# design.net
KiCad netlist of a schematic drawn in EasyEDA Pro
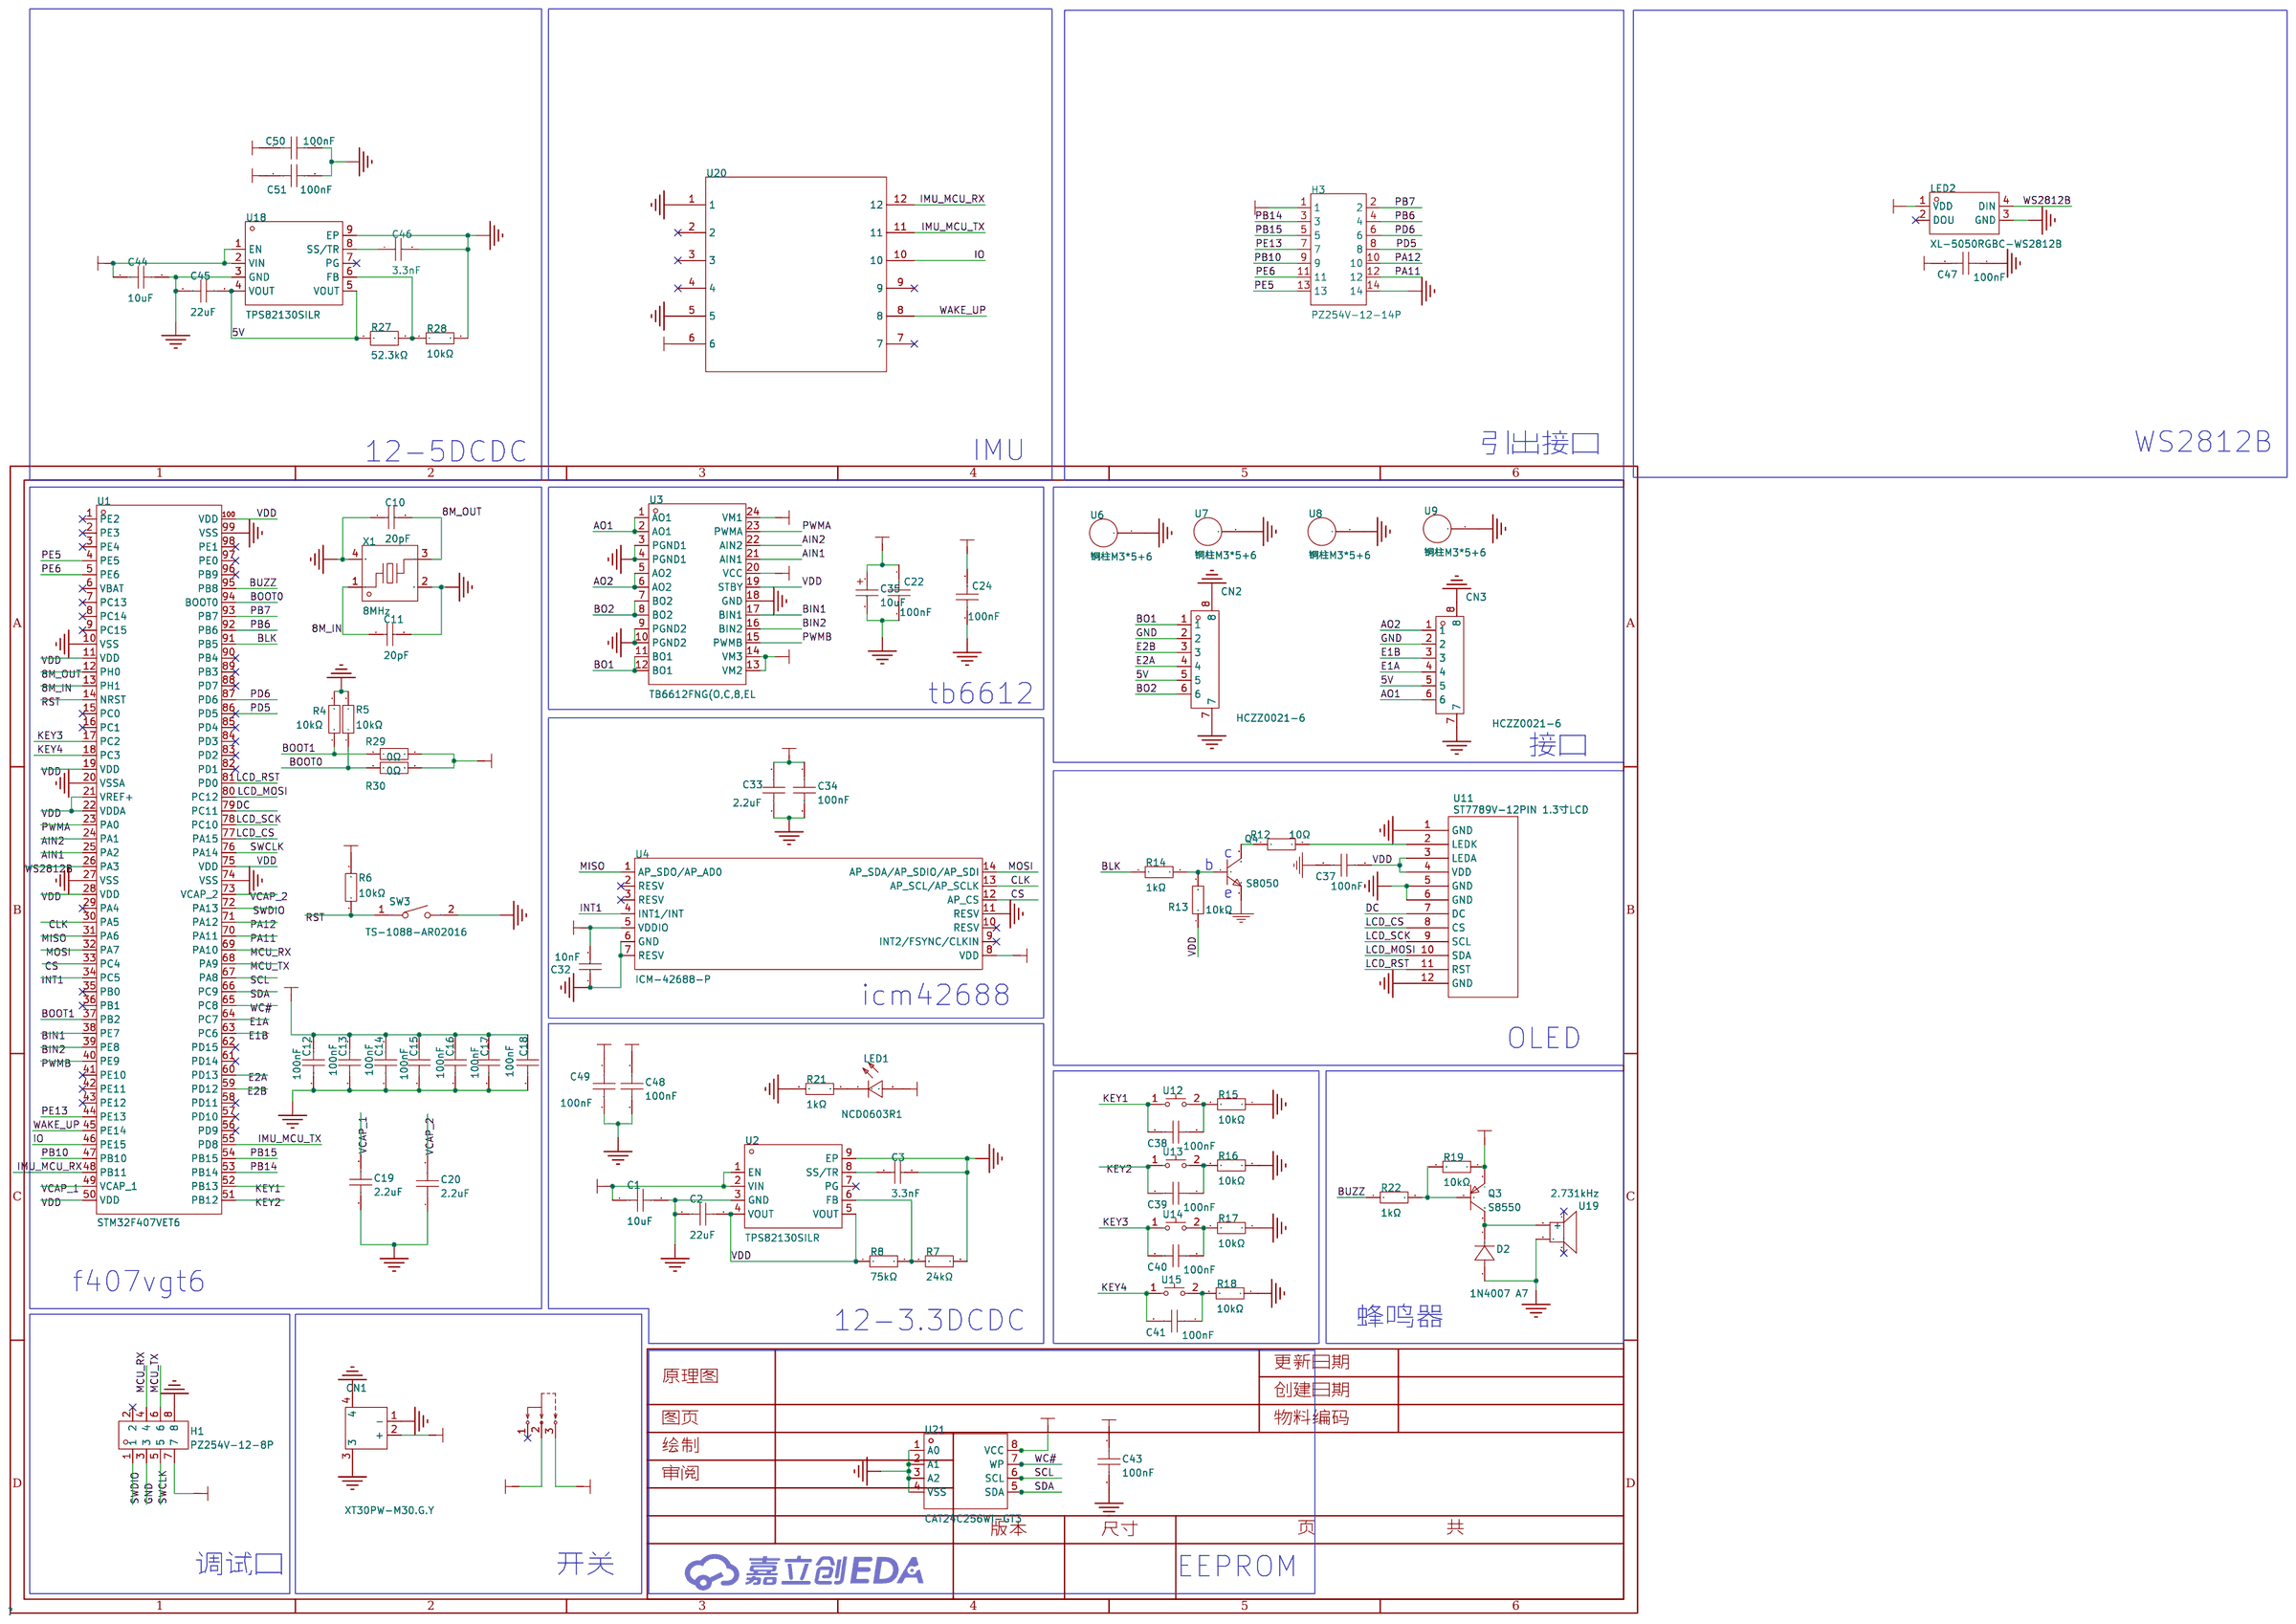
[diagram p0: schematic sheet]

(export (version "E")
  (design (tool "Eeschema 10.0.6"))
  (components
    (comp (ref "C1")
      (value "10uF")
      (footprint "easyedapro:C0805")
      (description "容值:10uF;精度:±10%;额定电压:50V;材质(温度系数):X5R;")
      (fields
        (field (name "Manufacturer Part") "GRM21BR61H106KE43L")
        (field (name "Manufacturer") "muRata(村田)")
      )
      (libsource (lib "easyedapro") (part "GRM21BR61H106KE43L"))
    )
    (comp (ref "C2")
      (value "22uF")
      (footprint "easyedapro:C0805")
      (description "容值:22uF;精度:±20%;额定电压:35V;材质(温度系数):X5R;")
      (fields
        (field (name "Manufacturer Part") "CGA0805X5R226M350MT")
        (field (name "Manufacturer") "HRE(芯声)")
      )
      (libsource (lib "easyedapro") (part "CGA0805X5R226M350MT"))
    )
    (comp (ref "C3")
      (value "3.3nF")
      (footprint "easyedapro:C0603")
      (description "容值:3.3nF;精度:±10%;额定电压:50V;材质(温度系数):X7R;")
      (fields
        (field (name "Manufacturer Part") "CC0603KRX7R9BB332")
        (field (name "Manufacturer") "YAGEO(国巨)")
      )
      (libsource (lib "easyedapro") (part "CC0603KRX7R9BB332"))
    )
    (comp (ref "C10")
      (value "20pF")
      (footprint "easyedapro:C0603")
      (description "容值:20pF;精度:±5%;额定电压:50V;材质(温度系数):C0G;")
      (fields
        (field (name "Manufacturer Part") "CL10C200JB8NNNC")
        (field (name "Manufacturer") "SAMSUNG(三星)")
      )
      (libsource (lib "easyedapro") (part "CL10C200JB8NNNC"))
    )
    (comp (ref "C11")
      (value "20pF")
      (footprint "easyedapro:C0603")
      (description "容值:20pF;精度:±5%;额定电压:50V;材质(温度系数):C0G;")
      (fields
        (field (name "Manufacturer Part") "CL10C200JB8NNNC")
        (field (name "Manufacturer") "SAMSUNG(三星)")
      )
      (libsource (lib "easyedapro") (part "CL10C200JB8NNNC"))
    )
    (comp (ref "C12")
      (value "100nF")
      (footprint "easyedapro:C0603")
      (description "容值:100nF;精度:±10%;额定电压:50V;材质(温度系数):X7R;")
      (fields
        (field (name "Manufacturer Part") "CGA0603X7R104K500JT")
        (field (name "Manufacturer") "HRE(芯声)")
      )
      (libsource (lib "easyedapro") (part "CGA0603X7R104K500JT"))
    )
    (comp (ref "C13")
      (value "100nF")
      (footprint "easyedapro:C0603")
      (description "容值:100nF;精度:±10%;额定电压:50V;材质(温度系数):X7R;")
      (fields
        (field (name "Manufacturer Part") "CGA0603X7R104K500JT")
        (field (name "Manufacturer") "HRE(芯声)")
      )
      (libsource (lib "easyedapro") (part "CGA0603X7R104K500JT"))
    )
    (comp (ref "C14")
      (value "100nF")
      (footprint "easyedapro:C0603")
      (description "容值:100nF;精度:±10%;额定电压:50V;材质(温度系数):X7R;")
      (fields
        (field (name "Manufacturer Part") "CGA0603X7R104K500JT")
        (field (name "Manufacturer") "HRE(芯声)")
      )
      (libsource (lib "easyedapro") (part "CGA0603X7R104K500JT"))
    )
    (comp (ref "C15")
      (value "100nF")
      (footprint "easyedapro:C0603")
      (description "容值:100nF;精度:±10%;额定电压:50V;材质(温度系数):X7R;")
      (fields
        (field (name "Manufacturer Part") "CGA0603X7R104K500JT")
        (field (name "Manufacturer") "HRE(芯声)")
      )
      (libsource (lib "easyedapro") (part "CGA0603X7R104K500JT"))
    )
    (comp (ref "C16")
      (value "100nF")
      (footprint "easyedapro:C0603")
      (description "容值:100nF;精度:±10%;额定电压:50V;材质(温度系数):X7R;")
      (fields
        (field (name "Manufacturer Part") "CGA0603X7R104K500JT")
        (field (name "Manufacturer") "HRE(芯声)")
      )
      (libsource (lib "easyedapro") (part "CGA0603X7R104K500JT"))
    )
    (comp (ref "C17")
      (value "100nF")
      (footprint "easyedapro:C0603")
      (description "容值:100nF;精度:±10%;额定电压:50V;材质(温度系数):X7R;")
      (fields
        (field (name "Manufacturer Part") "CGA0603X7R104K500JT")
        (field (name "Manufacturer") "HRE(芯声)")
      )
      (libsource (lib "easyedapro") (part "CGA0603X7R104K500JT"))
    )
    (comp (ref "C18")
      (value "100nF")
      (footprint "easyedapro:C0603")
      (description "容值:100nF;精度:±10%;额定电压:50V;材质(温度系数):X7R;")
      (fields
        (field (name "Manufacturer Part") "CGA0603X7R104K500JT")
        (field (name "Manufacturer") "HRE(芯声)")
      )
      (libsource (lib "easyedapro") (part "CGA0603X7R104K500JT"))
    )
    (comp (ref "C19")
      (value "2.2uF")
      (footprint "easyedapro:C0603")
      (description "容值:2.2uF;精度:±10%;额定电压:50V;材质(温度系数):X5R;")
      (fields
        (field (name "Manufacturer Part") "CL10A225KB8NNNC")
        (field (name "Manufacturer") "SAMSUNG(三星)")
      )
      (libsource (lib "easyedapro") (part "CL10A225KB8NNNC"))
    )
    (comp (ref "C20")
      (value "2.2uF")
      (footprint "easyedapro:C0603")
      (description "容值:2.2uF;精度:±10%;额定电压:50V;材质(温度系数):X5R;")
      (fields
        (field (name "Manufacturer Part") "CL10A225KB8NNNC")
        (field (name "Manufacturer") "SAMSUNG(三星)")
      )
      (libsource (lib "easyedapro") (part "CL10A225KB8NNNC"))
    )
    (comp (ref "C22")
      (value "100nF")
      (footprint "easyedapro:C0603")
      (description "容值:100nF;精度:±10%;额定电压:50V;材质(温度系数):X7R;")
      (fields
        (field (name "Manufacturer Part") "CGA0603X7R104K500JT")
        (field (name "Manufacturer") "HRE(芯声)")
      )
      (libsource (lib "easyedapro") (part "CGA0603X7R104K500JT"))
    )
    (comp (ref "C24")
      (value "100nF")
      (footprint "easyedapro:C0603")
      (description "容值:100nF;精度:±10%;额定电压:50V;材质(温度系数):X7R;")
      (fields
        (field (name "Manufacturer Part") "CGA0603X7R104K500JT")
        (field (name "Manufacturer") "HRE(芯声)")
      )
      (libsource (lib "easyedapro") (part "CGA0603X7R104K500JT"))
    )
    (comp (ref "C32")
      (value "10nF")
      (footprint "easyedapro:C0603")
      (description "容值:10nF;精度:±10%;额定电压:50V;材质(温度系数):X7R;")
      (fields
        (field (name "Manufacturer Part") "CC0603KRX7R9BB103")
        (field (name "Manufacturer") "YAGEO(国巨)")
      )
      (libsource (lib "easyedapro") (part "CC0603KRX7R9BB103"))
    )
    (comp (ref "C33")
      (value "2.2uF")
      (footprint "easyedapro:C0603")
      (description "容值:2.2uF;精度:±10%;额定电压:50V;材质(温度系数):X5R;")
      (fields
        (field (name "Manufacturer Part") "CL10A225KB8NNNC")
        (field (name "Manufacturer") "SAMSUNG(三星)")
      )
      (libsource (lib "easyedapro") (part "CL10A225KB8NNNC"))
    )
    (comp (ref "C34")
      (value "100nF")
      (footprint "easyedapro:C0603")
      (description "容值:100nF;精度:±10%;额定电压:50V;材质(温度系数):X7R;")
      (fields
        (field (name "Manufacturer Part") "CGA0603X7R104K500JT")
        (field (name "Manufacturer") "HRE(芯声)")
      )
      (libsource (lib "easyedapro") (part "CGA0603X7R104K500JT"))
    )
    (comp (ref "C35")
      (value "10uF")
      (footprint "easyedapro:CAP-SMD_L3.2-W1.6-RD-C7171")
      (description "容值:10uF;精度:±10%;额定电压:16V;等效串联电阻:3Ω@100kHz;")
      (fields (field (name "Manufacturer Part") "TAJA106K016RNJ") (field (name "Manufacturer") "Kyocera AVX"))
      (libsource (lib "easyedapro") (part "TAJA106K016RNJ"))
    )
    (comp (ref "C37")
      (value "100nF")
      (footprint "easyedapro:C0603")
      (description "容值:100nF;精度:±10%;额定电压:50V;材质(温度系数):X7R;")
      (fields
        (field (name "Manufacturer Part") "CGA0603X7R104K500JT")
        (field (name "Manufacturer") "HRE(芯声)")
      )
      (libsource (lib "easyedapro") (part "CGA0603X7R104K500JT"))
    )
    (comp (ref "C38")
      (value "100nF")
      (footprint "easyedapro:C0603")
      (description "容值:100nF;精度:±10%;额定电压:50V;材质(温度系数):X7R;")
      (fields
        (field (name "Manufacturer Part") "CGA0603X7R104K500JT")
        (field (name "Manufacturer") "HRE(芯声)")
      )
      (libsource (lib "easyedapro") (part "CGA0603X7R104K500JT"))
    )
    (comp (ref "C39")
      (value "100nF")
      (footprint "easyedapro:C0603")
      (description "容值:100nF;精度:±10%;额定电压:50V;材质(温度系数):X7R;")
      (fields
        (field (name "Manufacturer Part") "CGA0603X7R104K500JT")
        (field (name "Manufacturer") "HRE(芯声)")
      )
      (libsource (lib "easyedapro") (part "CGA0603X7R104K500JT"))
    )
    (comp (ref "C40")
      (value "100nF")
      (footprint "easyedapro:C0603")
      (description "容值:100nF;精度:±10%;额定电压:50V;材质(温度系数):X7R;")
      (fields
        (field (name "Manufacturer Part") "CGA0603X7R104K500JT")
        (field (name "Manufacturer") "HRE(芯声)")
      )
      (libsource (lib "easyedapro") (part "CGA0603X7R104K500JT"))
    )
    (comp (ref "C41")
      (value "100nF")
      (footprint "easyedapro:C0603")
      (description "容值:100nF;精度:±10%;额定电压:50V;材质(温度系数):X7R;")
      (fields
        (field (name "Manufacturer Part") "CGA0603X7R104K500JT")
        (field (name "Manufacturer") "HRE(芯声)")
      )
      (libsource (lib "easyedapro") (part "CGA0603X7R104K500JT"))
    )
    (comp (ref "C43")
      (value "100nF")
      (footprint "easyedapro:C0603")
      (description "容值:100nF;精度:±10%;额定电压:50V;材质(温度系数):X7R;")
      (fields
        (field (name "Manufacturer Part") "CGA0603X7R104K500JT")
        (field (name "Manufacturer") "HRE(芯声)")
      )
      (libsource (lib "easyedapro") (part "CGA0603X7R104K500JT"))
    )
    (comp (ref "C44")
      (value "10uF")
      (footprint "easyedapro:C0805")
      (description "容值:10uF;精度:±10%;额定电压:50V;材质(温度系数):X5R;")
      (fields
        (field (name "Manufacturer Part") "GRM21BR61H106KE43L")
        (field (name "Manufacturer") "muRata(村田)")
      )
      (libsource (lib "easyedapro") (part "GRM21BR61H106KE43L"))
    )
    (comp (ref "C45")
      (value "22uF")
      (footprint "easyedapro:C0805")
      (description "容值:22uF;精度:±20%;额定电压:35V;材质(温度系数):X5R;")
      (fields
        (field (name "Manufacturer Part") "CGA0805X5R226M350MT")
        (field (name "Manufacturer") "HRE(芯声)")
      )
      (libsource (lib "easyedapro") (part "CGA0805X5R226M350MT"))
    )
    (comp (ref "C46")
      (value "3.3nF")
      (footprint "easyedapro:C0603")
      (description "容值:3.3nF;精度:±10%;额定电压:50V;材质(温度系数):X7R;")
      (fields
        (field (name "Manufacturer Part") "CC0603KRX7R9BB332")
        (field (name "Manufacturer") "YAGEO(国巨)")
      )
      (libsource (lib "easyedapro") (part "CC0603KRX7R9BB332"))
    )
    (comp (ref "C47")
      (value "100nF")
      (footprint "easyedapro:C0603")
      (description "容值:100nF;精度:±10%;额定电压:50V;材质(温度系数):X7R;")
      (fields
        (field (name "Manufacturer Part") "CGA0603X7R104K500JT")
        (field (name "Manufacturer") "HRE(芯声)")
      )
      (libsource (lib "easyedapro") (part "CGA0603X7R104K500JT"))
    )
    (comp (ref "C48")
      (value "100nF")
      (footprint "easyedapro:C0603")
      (description "容值:100nF;精度:±10%;额定电压:50V;材质(温度系数):X7R;")
      (fields
        (field (name "Manufacturer Part") "CGA0603X7R104K500JT")
        (field (name "Manufacturer") "HRE(芯声)")
      )
      (libsource (lib "easyedapro") (part "CGA0603X7R104K500JT"))
    )
    (comp (ref "C49")
      (value "100nF")
      (footprint "easyedapro:C0603")
      (description "容值:100nF;精度:±10%;额定电压:50V;材质(温度系数):X7R;")
      (fields
        (field (name "Manufacturer Part") "CGA0603X7R104K500JT")
        (field (name "Manufacturer") "HRE(芯声)")
      )
      (libsource (lib "easyedapro") (part "CGA0603X7R104K500JT"))
    )
    (comp (ref "C50")
      (value "100nF")
      (footprint "easyedapro:C0603")
      (description "容值:100nF;精度:±10%;额定电压:50V;材质(温度系数):X7R;")
      (fields
        (field (name "Manufacturer Part") "CGA0603X7R104K500JT")
        (field (name "Manufacturer") "HRE(芯声)")
      )
      (libsource (lib "easyedapro") (part "CGA0603X7R104K500JT"))
    )
    (comp (ref "C51")
      (value "100nF")
      (footprint "easyedapro:C0603")
      (description "容值:100nF;精度:±10%;额定电压:50V;材质(温度系数):X7R;")
      (fields
        (field (name "Manufacturer Part") "CGA0603X7R104K500JT")
        (field (name "Manufacturer") "HRE(芯声)")
      )
      (libsource (lib "easyedapro") (part "CGA0603X7R104K500JT"))
    )
    (comp (ref "CN1")
      (value "XT30PW-M30.G.Y")
      (footprint "easyedapro:CONN-TH_XT30PW-M")
      (description "类别:-;类型1:-;")
      (fields (field (name "Manufacturer") "AMASS(艾迈斯)"))
      (libsource (lib "easyedapro") (part "XT30PW-M"))
    )
    (comp (ref "CN2")
      (value "HCZZ0021-6")
      (footprint "easyedapro:CONN-SMD_HCZZ0021-6")
      (fields (field (name "Manufacturer") "HC(虹成电子)"))
      (libsource (lib "easyedapro") (part "HCZZ0021-6"))
    )
    (comp (ref "CN3")
      (value "HCZZ0021-6")
      (footprint "easyedapro:CONN-SMD_HCZZ0021-6")
      (fields (field (name "Manufacturer") "HC(虹成电子)"))
      (libsource (lib "easyedapro") (part "HCZZ0021-6"))
    )
    (comp (ref "D2")
      (value "1N4007 A7")
      (footprint "easyedapro:SOD-123FL_L2.8-W1.8-LS3.7-RD")
      (description "二极管配置:-;正向压降(Vf):1V@1A;直流反向耐压(Vr):1kV;整流电流:1A;")
      (fields (field (name "Manufacturer") "MSKSEMI(美森科)"))
      (libsource (lib "easyedapro") (part "1N4007 A7"))
    )
    (comp (ref "H1")
      (value "PZ254V-12-8P")
      (footprint "easyedapro:HDR-TH_8P-P2.54-V-M-R2-C4-S2.54")
      (fields (field (name "Manufacturer") "XFCN(兴飞)"))
      (libsource (lib "easyedapro") (part "PZ254V-12-8P"))
    )
    (comp (ref "H3")
      (value "PZ254V-12-14P")
      (footprint "easyedapro:HDR-TH_14P-P2.54-V-M-R2-C7-S2.54")
      (fields (field (name "Manufacturer") "XFCN(兴飞)"))
      (libsource (lib "easyedapro") (part "PZ254V-12-14P"))
    )
    (comp (ref "LED1")
      (value "NCD0603R1")
      (footprint "easyedapro:LED0603-RD")
      (fields (field (name "Manufacturer") "国星光电"))
      (libsource (lib "easyedapro") (part "FC-DA1608HRK-620D"))
    )
    (comp (ref "LED2")
      (value "XL-5050RGBC-WS2812B")
      (footprint "easyedapro:LED-SMD_4P-L5.0-W5.0-BL_XL-5050RGBC")
      (description "5050七彩幻彩透明贴片LED灯珠 5050 幻彩透明四脚 ws2812B 内置驱动IC")
      (fields (field (name "Manufacturer") "XINGLIGHT(成兴光)"))
      (libsource (lib "easyedapro") (part "XL-5050RGBC-WS2812B"))
    )
    (comp (ref "Q3")
      (value "S8550")
      (footprint "easyedapro:SOT-23-3_L2.9-W1.6-P1.90-LS2.8-BR")
      (description "晶体管类型:PNP;集电极电流(Ic):500mA;集射极击穿电压(Vceo):25V;功率(Pd):300mW;")
      (fields (field (name "Manufacturer") "Hottech(合科泰)"))
      (libsource (lib "easyedapro") (part "S8550_C181159"))
    )
    (comp (ref "Q4")
      (value "S8050")
      (footprint "easyedapro:SOT-23-3_L2.9-W1.3-P1.90-LS2.3-BR")
      (description "晶体管类型:NPN;集电极电流(Ic):500mA;集射极击穿电压(Vceo):25V;功率(Pd):300mW;直流电流增益(hFE@Ic,Vce):120@50mA,1.0V;")
      (fields (field (name "Manufacturer") "宏迦橙"))
      (libsource (lib "easyedapro") (part "S8050_C20069125"))
    )
    (comp (ref "R4")
      (value "10kΩ")
      (footprint "easyedapro:R0603")
      (description "电阻类型:厚膜电阻;阻值:10kΩ;精度:±1%;功率:100mW;最大工作电压:75V;温度系数:±100ppm/°C;")
      (fields
        (field (name "Manufacturer Part") "0603WAF1002T5E")
        (field (name "Manufacturer") "UNI-ROYAL(厚声)")
      )
      (libsource (lib "easyedapro") (part "0603WAF1002T5E"))
    )
    (comp (ref "R5")
      (value "10kΩ")
      (footprint "easyedapro:R0603")
      (description "电阻类型:厚膜电阻;阻值:10kΩ;精度:±1%;功率:100mW;最大工作电压:75V;温度系数:±100ppm/°C;")
      (fields
        (field (name "Manufacturer Part") "0603WAF1002T5E")
        (field (name "Manufacturer") "UNI-ROYAL(厚声)")
      )
      (libsource (lib "easyedapro") (part "0603WAF1002T5E"))
    )
    (comp (ref "R6")
      (value "10kΩ")
      (footprint "easyedapro:R0603")
      (description "电阻类型:厚膜电阻;阻值:10kΩ;精度:±1%;功率:100mW;最大工作电压:75V;温度系数:±100ppm/°C;")
      (fields
        (field (name "Manufacturer Part") "0603WAF1002T5E")
        (field (name "Manufacturer") "UNI-ROYAL(厚声)")
      )
      (libsource (lib "easyedapro") (part "0603WAF1002T5E"))
    )
    (comp (ref "R7")
      (value "24kΩ")
      (footprint "easyedapro:R0603")
      (description "电阻类型:厚膜电阻;阻值:24kΩ;精度:±1%;功率:100mW;最大工作电压:75V;温度系数:±100ppm/°C;")
      (fields
        (field (name "Manufacturer Part") "0603WAF2402T5E")
        (field (name "Manufacturer") "UNI-ROYAL(厚声)")
      )
      (libsource (lib "easyedapro") (part "0603WAF2402T5E"))
    )
    (comp (ref "R8")
      (value "75kΩ")
      (footprint "easyedapro:R0603")
      (description "电阻类型:厚膜电阻;阻值:75kΩ;精度:±1%;功率:100mW;最大工作电压:75V;温度系数:±100ppm/°C;")
      (fields
        (field (name "Manufacturer Part") "0603WAF7502T5E")
        (field (name "Manufacturer") "UNI-ROYAL(厚声)")
      )
      (libsource (lib "easyedapro") (part "0603WAF7502T5E"))
    )
    (comp (ref "R12")
      (value "10Ω")
      (footprint "easyedapro:R0603")
      (description "电阻类型:厚膜电阻;阻值:10Ω;精度:±1%;功率:100mW;最大工作电压:75V;温度系数:±400ppm/°C;")
      (fields
        (field (name "Manufacturer Part") "0603WAF100JT5E")
        (field (name "Manufacturer") "UNI-ROYAL(厚声)")
      )
      (libsource (lib "easyedapro") (part "0603WAF100JT5E"))
    )
    (comp (ref "R13")
      (value "10kΩ")
      (footprint "easyedapro:R0603")
      (description "电阻类型:厚膜电阻;阻值:10kΩ;精度:±1%;功率:100mW;最大工作电压:75V;温度系数:±100ppm/°C;")
      (fields
        (field (name "Manufacturer Part") "0603WAF1002T5E")
        (field (name "Manufacturer") "UNI-ROYAL(厚声)")
      )
      (libsource (lib "easyedapro") (part "0603WAF1002T5E"))
    )
    (comp (ref "R14")
      (value "1kΩ")
      (footprint "easyedapro:R0603")
      (description "电阻类型:厚膜电阻;阻值:1kΩ;精度:±1%;功率:100mW;最大工作电压:75V;温度系数:±100ppm/°C;")
      (fields
        (field (name "Manufacturer Part") "0603WAF1001T5E")
        (field (name "Manufacturer") "UNI-ROYAL(厚声)")
      )
      (libsource (lib "easyedapro") (part "0603WAF1001T5E"))
    )
    (comp (ref "R15")
      (value "10kΩ")
      (footprint "easyedapro:R0603")
      (description "电阻类型:厚膜电阻;阻值:10kΩ;精度:±1%;功率:100mW;最大工作电压:75V;温度系数:±100ppm/°C;")
      (fields
        (field (name "Manufacturer Part") "0603WAF1002T5E")
        (field (name "Manufacturer") "UNI-ROYAL(厚声)")
      )
      (libsource (lib "easyedapro") (part "0603WAF1002T5E"))
    )
    (comp (ref "R16")
      (value "10kΩ")
      (footprint "easyedapro:R0603")
      (description "电阻类型:厚膜电阻;阻值:10kΩ;精度:±1%;功率:100mW;最大工作电压:75V;温度系数:±100ppm/°C;")
      (fields
        (field (name "Manufacturer Part") "0603WAF1002T5E")
        (field (name "Manufacturer") "UNI-ROYAL(厚声)")
      )
      (libsource (lib "easyedapro") (part "0603WAF1002T5E"))
    )
    (comp (ref "R17")
      (value "10kΩ")
      (footprint "easyedapro:R0603")
      (description "电阻类型:厚膜电阻;阻值:10kΩ;精度:±1%;功率:100mW;最大工作电压:75V;温度系数:±100ppm/°C;")
      (fields
        (field (name "Manufacturer Part") "0603WAF1002T5E")
        (field (name "Manufacturer") "UNI-ROYAL(厚声)")
      )
      (libsource (lib "easyedapro") (part "0603WAF1002T5E"))
    )
    (comp (ref "R18")
      (value "10kΩ")
      (footprint "easyedapro:R0603")
      (description "电阻类型:厚膜电阻;阻值:10kΩ;精度:±1%;功率:100mW;最大工作电压:75V;温度系数:±100ppm/°C;")
      (fields
        (field (name "Manufacturer Part") "0603WAF1002T5E")
        (field (name "Manufacturer") "UNI-ROYAL(厚声)")
      )
      (libsource (lib "easyedapro") (part "0603WAF1002T5E"))
    )
    (comp (ref "R19")
      (value "10kΩ")
      (footprint "easyedapro:R0603")
      (description "电阻类型:厚膜电阻;阻值:10kΩ;精度:±1%;功率:100mW;最大工作电压:75V;温度系数:±100ppm/°C;")
      (fields
        (field (name "Manufacturer Part") "0603WAF1002T5E")
        (field (name "Manufacturer") "UNI-ROYAL(厚声)")
      )
      (libsource (lib "easyedapro") (part "0603WAF1002T5E"))
    )
    (comp (ref "R21")
      (value "1kΩ")
      (footprint "easyedapro:R0603")
      (description "电阻类型:厚膜电阻;阻值:1kΩ;精度:±1%;功率:100mW;最大工作电压:75V;温度系数:±100ppm/°C;")
      (fields
        (field (name "Manufacturer Part") "0603WAF1001T5E")
        (field (name "Manufacturer") "UNI-ROYAL(厚声)")
      )
      (libsource (lib "easyedapro") (part "0603WAF1001T5E"))
    )
    (comp (ref "R22")
      (value "1kΩ")
      (footprint "easyedapro:R0603")
      (description "电阻类型:厚膜电阻;阻值:1kΩ;精度:±1%;功率:100mW;最大工作电压:75V;温度系数:±100ppm/°C;")
      (fields
        (field (name "Manufacturer Part") "0603WAF1001T5E")
        (field (name "Manufacturer") "UNI-ROYAL(厚声)")
      )
      (libsource (lib "easyedapro") (part "0603WAF1001T5E"))
    )
    (comp (ref "R27")
      (value "52.3kΩ")
      (footprint "easyedapro:R0603")
      (description "电阻类型:薄膜电阻;阻值:52.3kΩ;精度:±0.1%;功率:100mW;最大工作电压:75V;温度系数:±25ppm/°C;")
      (fields (field (name "Manufacturer Part") "ERA3AEB5232V") (field (name "Manufacturer") "PANASONIC(松下)"))
      (libsource (lib "easyedapro") (part "ERA3AEB5232V"))
    )
    (comp (ref "R28")
      (value "10kΩ")
      (footprint "easyedapro:R0603")
      (description "电阻类型:厚膜电阻;阻值:10kΩ;精度:±1%;功率:100mW;最大工作电压:75V;温度系数:±100ppm/°C;")
      (fields
        (field (name "Manufacturer Part") "0603WAF1002T5E")
        (field (name "Manufacturer") "UNI-ROYAL(厚声)")
      )
      (libsource (lib "easyedapro") (part "0603WAF1002T5E"))
    )
    (comp (ref "R29")
      (value "0Ω")
      (footprint "easyedapro:R0603")
      (description "电阻类型:厚膜电阻;阻值:0Ω;精度:±1%;功率:100mW;最大工作电压:75V;")
      (fields
        (field (name "Manufacturer Part") "0603WAF0000T5E")
        (field (name "Manufacturer") "UNI-ROYAL(厚声)")
      )
      (libsource (lib "easyedapro") (part "0603WAF0000T5E"))
    )
    (comp (ref "R30")
      (value "0Ω")
      (footprint "easyedapro:R0603")
      (description "电阻类型:厚膜电阻;阻值:0Ω;精度:±1%;功率:100mW;最大工作电压:75V;")
      (fields
        (field (name "Manufacturer Part") "0603WAF0000T5E")
        (field (name "Manufacturer") "UNI-ROYAL(厚声)")
      )
      (libsource (lib "easyedapro") (part "0603WAF0000T5E"))
    )
    (comp (ref "SW3")
      (value "TS-1088-AR02016")
      (footprint "easyedapro:SW-SMD_L3.9-W3.0-P4.45")
      (fields (field (name "Manufacturer") "XUNPU(讯普)"))
      (libsource (lib "easyedapro") (part "TS-1088-AR02016"))
    )
    (comp (ref "U1")
      (value "STM32F407VET6")
      (footprint "easyedapro:LQFP-100_L14.0-W14.0-P0.50-LS16.0-BL")
      (description "CPU内核:ARM-M4;程序存储容量:1MB;RAM总容量:192KB;GPIO端口数量:82;工作电压范围:1.8V~3.6V;CPU最大主频:168MHz;程序存储器类型:FLASH;")
      (fields (field (name "Manufacturer") "ST(意法半导体)"))
      (libsource (lib "easyedapro") (part "STM32F407VGT6"))
    )
    (comp (ref "U2")
      (value "TPS82130SILR")
      (footprint "easyedapro:USIP-8_L3.0-W2.8-P0.65-TL-EP")
      (description "TPS82130 TPS82130 具有集成电感的 3A 17V 降压转换器")
      (fields (field (name "Manufacturer") "TI(德州仪器)"))
      (libsource (lib "easyedapro") (part "TPS82130SILR"))
    )
    (comp (ref "U3")
      (value "TB6612FNG(O,C,8,EL")
      (footprint "easyedapro:SSOP-24_L8.4-W5.8-P0.65-LS7.8-BL")
      (description "双直流电机驱动器集成电路")
      (fields (field (name "Manufacturer") "TOSHIBA(东芝)"))
      (libsource (lib "easyedapro") (part "TB6612FNG(O,C,8,EL"))
    )
    (comp (ref "U4")
      (value "ICM-42688-P")
      (footprint "easyedapro:LGA-14_L3.0-W2.5-P0.50-TL")
      (description "传感器类型:加速度计陀螺仪;")
      (fields (field (name "Manufacturer") "TDK InvenSense(应美盛)"))
      (libsource (lib "easyedapro") (part "ICM-42688-P"))
    )
    (comp (ref "U6")
      (value "铜柱M3*5+6")
      (footprint "easyedapro:SMD_BD4.2-L4.7-W4.7-D3.0")
      (description "M3*5+6")
      (fields (field (name "Manufacturer") "国产"))
      (libsource (lib "easyedapro") (part "铜柱M3*5+6"))
    )
    (comp (ref "U7")
      (value "铜柱M3*5+6")
      (footprint "easyedapro:SMD_BD4.2-L4.7-W4.7-D3.0")
      (description "M3*5+6")
      (fields (field (name "Manufacturer") "国产"))
      (libsource (lib "easyedapro") (part "铜柱M3*5+6"))
    )
    (comp (ref "U8")
      (value "铜柱M3*5+6")
      (footprint "easyedapro:SMD_BD4.2-L4.7-W4.7-D3.0")
      (description "M3*5+6")
      (fields (field (name "Manufacturer") "国产"))
      (libsource (lib "easyedapro") (part "铜柱M3*5+6"))
    )
    (comp (ref "U9")
      (value "铜柱M3*5+6")
      (footprint "easyedapro:SMD_BD4.2-L4.7-W4.7-D3.0")
      (description "M3*5+6")
      (fields (field (name "Manufacturer") "国产"))
      (libsource (lib "easyedapro") (part "铜柱M3*5+6"))
    )
    (comp (ref "U11")
      (value "ST7789V-12PIN 1.3寸LCD")
      (footprint "easyedapro:ST7789V-12PIN")
      (libsource (lib "easyedapro") (part "ST7789V-12PIN 1.3寸LCD"))
    )
    (comp (ref "U12")
      (value "TS-1199A26050")
      (footprint "easyedapro:SW-SMD_L6.0-W6.0-LS6.6")
      (fields (field (name "Manufacturer") "HanElectricity(瀚源)"))
      (libsource (lib "easyedapro") (part "TS-1199A26050"))
    )
    (comp (ref "U13")
      (value "TS-1199A26050")
      (footprint "easyedapro:SW-SMD_L6.0-W6.0-LS6.6")
      (fields (field (name "Manufacturer") "HanElectricity(瀚源)"))
      (libsource (lib "easyedapro") (part "TS-1199A26050"))
    )
    (comp (ref "U14")
      (value "TS-1199A26050")
      (footprint "easyedapro:SW-SMD_L6.0-W6.0-LS6.6")
      (fields (field (name "Manufacturer") "HanElectricity(瀚源)"))
      (libsource (lib "easyedapro") (part "TS-1199A26050"))
    )
    (comp (ref "U15")
      (value "TS-1199A26050")
      (footprint "easyedapro:SW-SMD_L6.0-W6.0-LS6.6")
      (fields (field (name "Manufacturer") "HanElectricity(瀚源)"))
      (libsource (lib "easyedapro") (part "TS-1199A26050"))
    )
    (comp (ref "U16")
      (value "SS12D10G5")
      (footprint "easyedapro:SW-TH_SHOU-HAN_SS12D10G4")
      (description "电路结构:单刀双掷;安装方式:直插;额定电流(DC):2A;额定电压(DC):125V;机械寿命:3千次;")
      (fields (field (name "Manufacturer") "SHOU HAN(首韩)"))
      (libsource (lib "easyedapro") (part "SS12D10G5"))
    )
    (comp (ref "U18")
      (value "TPS82130SILR")
      (footprint "easyedapro:USIP-8_L3.0-W2.8-P0.65-TL-EP")
      (description "TPS82130 TPS82130 具有集成电感的 3A 17V 降压转换器")
      (fields (field (name "Manufacturer") "TI(德州仪器)"))
      (libsource (lib "easyedapro") (part "TPS82130SILR"))
    )
    (comp (ref "U19")
      (value "2.731kHz")
      (footprint "easyedapro:BUZ-SMD_4P-L8.5-W8.5-P8.50-TL-A")
      (description "频率:2.731kHz;声压(SPL):85dB;")
      (fields (field (name "Manufacturer Part") "HYG-8503A-5027") (field (name "Manufacturer") "HYDZ(华宇)"))
      (libsource (lib "easyedapro") (part "HYG-8503A-5027"))
    )
    (comp (ref "U20")
      (value "~")
      (footprint "easyedapro:15轴imu")
      (libsource (lib "easyedapro") (part "15轴imu"))
    )
    (comp (ref "U21")
      (value "CAT24C256WI-GT3")
      (footprint "easyedapro:SOIC-8_L4.9-W3.9-P1.27-LS6.0-BL")
      (description "接口类型:I2C;存储容量:256Kbit;")
      (fields (field (name "Manufacturer") "onsemi(安森美)"))
      (libsource (lib "easyedapro") (part "CAT24C256WI-GT3"))
    )
    (comp (ref "X1")
      (value "8MHz")
      (footprint "easyedapro:OSC-SMD_4P-L3.2-W2.5-BL")
      (description "晶振类型:贴片晶振;频率:8MHz;常温频差:±10ppm;外接负载电容:12pF;频率稳定度(全温):±20ppm;")
      (fields (field (name "Manufacturer Part") "X32258MOB4SI") (field (name "Manufacturer") "YXC(扬兴晶振)"))
      (libsource (lib "easyedapro") (part "X32258MOB4SI"))
    )
  )
  (nets
    (net (code "1") (name "/8M_IN") (class "Default")
      (node (ref "C11") (pin "1") (pinfunction "1_1") (pintype "input"))
      (node (ref "U1") (pin "13") (pinfunction "PH1_13") (pintype "unspecified"))
      (node (ref "X1") (pin "1") (pinfunction "1_1") (pintype "input"))
    )
    (net (code "2") (name "/8M_OUT") (class "Default")
      (node (ref "C10") (pin "2") (pinfunction "2_2") (pintype "input"))
      (node (ref "U1") (pin "12") (pinfunction "PH0_12") (pintype "unspecified"))
      (node (ref "X1") (pin "3") (pinfunction "3_3") (pintype "input"))
    )
    (net (code "3") (name "/AIN1") (class "Default")
      (node (ref "U1") (pin "25") (pinfunction "PA2_25") (pintype "unspecified"))
      (node (ref "U3") (pin "21") (pinfunction "AIN1_21") (pintype "unspecified"))
    )
    (net (code "4") (name "/AIN2") (class "Default")
      (node (ref "U1") (pin "24") (pinfunction "PA1_24") (pintype "unspecified"))
      (node (ref "U3") (pin "22") (pinfunction "AIN2_22") (pintype "unspecified"))
    )
    (net (code "5") (name "/AO1") (class "Default")
      (node (ref "CN3") (pin "6") (pinfunction "6_6") (pintype "unspecified"))
      (node (ref "U3") (pin "1") (pinfunction "AO1_1") (pintype "unspecified"))
      (node (ref "U3") (pin "2") (pinfunction "AO1_2") (pintype "unspecified"))
    )
    (net (code "6") (name "/AO2") (class "Default")
      (node (ref "CN3") (pin "1") (pinfunction "1_1") (pintype "unspecified"))
      (node (ref "U3") (pin "5") (pinfunction "AO2_5") (pintype "unspecified"))
      (node (ref "U3") (pin "6") (pinfunction "AO2_6") (pintype "unspecified"))
    )
    (net (code "7") (name "/BIN1") (class "Default")
      (node (ref "U1") (pin "38") (pinfunction "PE7_38") (pintype "unspecified"))
      (node (ref "U3") (pin "17") (pinfunction "BIN1_17") (pintype "unspecified"))
    )
    (net (code "8") (name "/BIN2") (class "Default")
      (node (ref "U1") (pin "39") (pinfunction "PE8_39") (pintype "unspecified"))
      (node (ref "U3") (pin "16") (pinfunction "BIN2_16") (pintype "unspecified"))
    )
    (net (code "9") (name "/BLK") (class "Default")
      (node (ref "R14") (pin "1") (pinfunction "1_1") (pintype "input"))
      (node (ref "U1") (pin "91") (pinfunction "PB5_91") (pintype "unspecified"))
    )
    (net (code "10") (name "/BO1") (class "Default")
      (node (ref "CN2") (pin "1") (pinfunction "1_1") (pintype "unspecified"))
      (node (ref "U3") (pin "11") (pinfunction "BO1_11") (pintype "unspecified"))
      (node (ref "U3") (pin "12") (pinfunction "BO1_12") (pintype "unspecified"))
    )
    (net (code "11") (name "/BO2") (class "Default")
      (node (ref "CN2") (pin "6") (pinfunction "6_6") (pintype "unspecified"))
      (node (ref "U3") (pin "7") (pinfunction "BO2_7") (pintype "unspecified"))
      (node (ref "U3") (pin "8") (pinfunction "BO2_8") (pintype "unspecified"))
    )
    (net (code "12") (name "/BOOT0") (class "Default")
      (node (ref "R30") (pin "1") (pinfunction "1_1") (pintype "input"))
      (node (ref "R5") (pin "1") (pinfunction "1_1") (pintype "input"))
      (node (ref "U1") (pin "94") (pinfunction "BOOT0_94") (pintype "unspecified"))
    )
    (net (code "13") (name "/BOOT1") (class "Default")
      (node (ref "R29") (pin "1") (pinfunction "1_1") (pintype "input"))
      (node (ref "R4") (pin "1") (pinfunction "1_1") (pintype "input"))
      (node (ref "U1") (pin "37") (pinfunction "PB2_37") (pintype "unspecified"))
    )
    (net (code "14") (name "/BUZZ") (class "Default")
      (node (ref "R22") (pin "1") (pinfunction "1_1") (pintype "input"))
      (node (ref "U1") (pin "95") (pinfunction "PB8_95") (pintype "unspecified"))
    )
    (net (code "15") (name "/CLK") (class "Default")
      (node (ref "U1") (pin "30") (pinfunction "PA5_30") (pintype "unspecified"))
      (node (ref "U4") (pin "13") (pinfunction "AP_SCL/AP_SCLK_13") (pintype "unspecified"))
    )
    (net (code "16") (name "/CS") (class "Default")
      (node (ref "U1") (pin "33") (pinfunction "PC4_33") (pintype "unspecified"))
      (node (ref "U4") (pin "12") (pinfunction "AP_CS_12") (pintype "unspecified"))
    )
    (net (code "17") (name "/DC") (class "Default")
      (node (ref "U1") (pin "79") (pinfunction "PC11_79") (pintype "unspecified"))
      (node (ref "U11") (pin "7") (pinfunction "DC_7") (pintype "unspecified"))
    )
    (net (code "18") (name "/E1A") (class "Default")
      (node (ref "CN3") (pin "4") (pinfunction "4_4") (pintype "unspecified"))
      (node (ref "U1") (pin "64") (pinfunction "PC7_64") (pintype "unspecified"))
    )
    (net (code "19") (name "/E1B") (class "Default")
      (node (ref "CN3") (pin "3") (pinfunction "3_3") (pintype "unspecified"))
      (node (ref "U1") (pin "63") (pinfunction "PC6_63") (pintype "unspecified"))
    )
    (net (code "20") (name "/E2A") (class "Default")
      (node (ref "CN2") (pin "4") (pinfunction "4_4") (pintype "unspecified"))
      (node (ref "U1") (pin "60") (pinfunction "PD13_60") (pintype "unspecified"))
    )
    (net (code "21") (name "/E2B") (class "Default")
      (node (ref "CN2") (pin "3") (pinfunction "3_3") (pintype "unspecified"))
      (node (ref "U1") (pin "59") (pinfunction "PD12_59") (pintype "unspecified"))
    )
    (net (code "22") (name "/IMU_MCU_RX") (class "Default")
      (node (ref "U1") (pin "48") (pinfunction "PB11_48") (pintype "unspecified"))
      (node (ref "U20") (pin "12") (pinfunction "12_12") (pintype "input"))
    )
    (net (code "23") (name "/IMU_MCU_TX") (class "Default")
      (node (ref "U1") (pin "55") (pinfunction "PD8_55") (pintype "unspecified"))
      (node (ref "U20") (pin "11") (pinfunction "11_11") (pintype "input"))
    )
    (net (code "24") (name "/INT1") (class "Default")
      (node (ref "U1") (pin "34") (pinfunction "PC5_34") (pintype "unspecified"))
      (node (ref "U4") (pin "4") (pinfunction "INT1/INT_4") (pintype "unspecified"))
    )
    (net (code "25") (name "/IO") (class "Default")
      (node (ref "U1") (pin "46") (pinfunction "PE15_46") (pintype "unspecified"))
      (node (ref "U20") (pin "10") (pinfunction "10_10") (pintype "input"))
    )
    (net (code "26") (name "/KEY1") (class "Default")
      (node (ref "C38") (pin "2") (pinfunction "2_2") (pintype "unspecified"))
      (node (ref "U1") (pin "52") (pinfunction "PB13_52") (pintype "unspecified"))
      (node (ref "U12") (pin "1") (pinfunction "1_1") (pintype "unspecified"))
    )
    (net (code "27") (name "/KEY2") (class "Default")
      (node (ref "C39") (pin "2") (pinfunction "2_2") (pintype "unspecified"))
      (node (ref "U1") (pin "51") (pinfunction "PB12_51") (pintype "unspecified"))
      (node (ref "U13") (pin "1") (pinfunction "1_1") (pintype "unspecified"))
    )
    (net (code "28") (name "/KEY3") (class "Default")
      (node (ref "C40") (pin "2") (pinfunction "2_2") (pintype "unspecified"))
      (node (ref "U1") (pin "17") (pinfunction "PC2_17") (pintype "unspecified"))
      (node (ref "U14") (pin "1") (pinfunction "1_1") (pintype "unspecified"))
    )
    (net (code "29") (name "/KEY4") (class "Default")
      (node (ref "C41") (pin "2") (pinfunction "2_2") (pintype "unspecified"))
      (node (ref "U1") (pin "18") (pinfunction "PC3_18") (pintype "unspecified"))
      (node (ref "U15") (pin "1") (pinfunction "1_1") (pintype "unspecified"))
    )
    (net (code "30") (name "/LCD_CS") (class "Default")
      (node (ref "U1") (pin "77") (pinfunction "PA15_77") (pintype "unspecified"))
      (node (ref "U11") (pin "8") (pinfunction "CS_8") (pintype "unspecified"))
    )
    (net (code "31") (name "/LCD_MOSI") (class "Default")
      (node (ref "U1") (pin "80") (pinfunction "PC12_80") (pintype "unspecified"))
      (node (ref "U11") (pin "10") (pinfunction "SDA_10") (pintype "unspecified"))
    )
    (net (code "32") (name "/LCD_RST") (class "Default")
      (node (ref "U1") (pin "81") (pinfunction "PD0_81") (pintype "unspecified"))
      (node (ref "U11") (pin "11") (pinfunction "RST_11") (pintype "unspecified"))
    )
    (net (code "33") (name "/LCD_SCK") (class "Default")
      (node (ref "U1") (pin "78") (pinfunction "PC10_78") (pintype "unspecified"))
      (node (ref "U11") (pin "9") (pinfunction "SCL_9") (pintype "unspecified"))
    )
    (net (code "34") (name "/MCU_RX") (class "Default")
      (node (ref "H1") (pin "4") (pinfunction "4_4") (pintype "unspecified"))
      (node (ref "U1") (pin "69") (pinfunction "PA10_69") (pintype "unspecified"))
    )
    (net (code "35") (name "/MCU_TX") (class "Default")
      (node (ref "H1") (pin "6") (pinfunction "6_6") (pintype "unspecified"))
      (node (ref "U1") (pin "68") (pinfunction "PA9_68") (pintype "unspecified"))
    )
    (net (code "36") (name "/MISO") (class "Default")
      (node (ref "U1") (pin "31") (pinfunction "PA6_31") (pintype "unspecified"))
      (node (ref "U4") (pin "1") (pinfunction "AP_SDO/AP_AD0_1") (pintype "unspecified"))
    )
    (net (code "37") (name "/MOSI") (class "Default")
      (node (ref "U1") (pin "32") (pinfunction "PA7_32") (pintype "unspecified"))
      (node (ref "U4") (pin "14") (pinfunction "AP_SDA/AP_SDIO/AP_SDI_14") (pintype "unspecified"))
    )
    (net (code "38") (name "/PA11") (class "Default")
      (node (ref "H3") (pin "12") (pinfunction "12_12") (pintype "unspecified"))
      (node (ref "U1") (pin "70") (pinfunction "PA11_70") (pintype "unspecified"))
    )
    (net (code "39") (name "/PA12") (class "Default")
      (node (ref "H3") (pin "10") (pinfunction "10_10") (pintype "unspecified"))
      (node (ref "U1") (pin "71") (pinfunction "PA12_71") (pintype "unspecified"))
    )
    (net (code "40") (name "/PB6") (class "Default")
      (node (ref "H3") (pin "4") (pinfunction "4_4") (pintype "unspecified"))
      (node (ref "U1") (pin "92") (pinfunction "PB6_92") (pintype "unspecified"))
    )
    (net (code "41") (name "/PB7") (class "Default")
      (node (ref "H3") (pin "2") (pinfunction "2_2") (pintype "unspecified"))
      (node (ref "U1") (pin "93") (pinfunction "PB7_93") (pintype "unspecified"))
    )
    (net (code "42") (name "/PB10") (class "Default")
      (node (ref "H3") (pin "9") (pinfunction "9_9") (pintype "unspecified"))
      (node (ref "U1") (pin "47") (pinfunction "PB10_47") (pintype "unspecified"))
    )
    (net (code "43") (name "/PB14") (class "Default")
      (node (ref "H3") (pin "3") (pinfunction "3_3") (pintype "unspecified"))
      (node (ref "U1") (pin "53") (pinfunction "PB14_53") (pintype "unspecified"))
    )
    (net (code "44") (name "/PB15") (class "Default")
      (node (ref "H3") (pin "5") (pinfunction "5_5") (pintype "unspecified"))
      (node (ref "U1") (pin "54") (pinfunction "PB15_54") (pintype "unspecified"))
    )
    (net (code "45") (name "/PD5") (class "Default")
      (node (ref "H3") (pin "8") (pinfunction "8_8") (pintype "unspecified"))
      (node (ref "U1") (pin "86") (pinfunction "PD5_86") (pintype "unspecified"))
    )
    (net (code "46") (name "/PD6") (class "Default")
      (node (ref "H3") (pin "6") (pinfunction "6_6") (pintype "unspecified"))
      (node (ref "U1") (pin "87") (pinfunction "PD6_87") (pintype "unspecified"))
    )
    (net (code "47") (name "/PE5") (class "Default")
      (node (ref "H3") (pin "13") (pinfunction "13_13") (pintype "unspecified"))
      (node (ref "U1") (pin "4") (pinfunction "PE5_4") (pintype "unspecified"))
    )
    (net (code "48") (name "/PE6") (class "Default")
      (node (ref "H3") (pin "11") (pinfunction "11_11") (pintype "unspecified"))
      (node (ref "U1") (pin "5") (pinfunction "PE6_5") (pintype "unspecified"))
    )
    (net (code "49") (name "/PE13") (class "Default")
      (node (ref "H3") (pin "7") (pinfunction "7_7") (pintype "unspecified"))
      (node (ref "U1") (pin "44") (pinfunction "PE13_44") (pintype "unspecified"))
    )
    (net (code "50") (name "/PWMA") (class "Default")
      (node (ref "U1") (pin "23") (pinfunction "PA0_23") (pintype "unspecified"))
      (node (ref "U3") (pin "23") (pinfunction "PWMA_23") (pintype "unspecified"))
    )
    (net (code "51") (name "/PWMB") (class "Default")
      (node (ref "U1") (pin "40") (pinfunction "PE9_40") (pintype "unspecified"))
      (node (ref "U3") (pin "15") (pinfunction "PWMB_15") (pintype "unspecified"))
    )
    (net (code "52") (name "/RST") (class "Default")
      (node (ref "R6") (pin "1") (pinfunction "1_1") (pintype "input"))
      (node (ref "SW3") (pin "1") (pinfunction "1_1") (pintype "unspecified"))
      (node (ref "U1") (pin "14") (pinfunction "NRST_14") (pintype "unspecified"))
    )
    (net (code "53") (name "/SCL") (class "Default")
      (node (ref "U1") (pin "67") (pinfunction "PA8_67") (pintype "unspecified"))
      (node (ref "U21") (pin "6") (pinfunction "SCL_6") (pintype "unspecified"))
    )
    (net (code "54") (name "/SDA") (class "Default")
      (node (ref "U1") (pin "66") (pinfunction "PC9_66") (pintype "unspecified"))
      (node (ref "U21") (pin "5") (pinfunction "SDA_5") (pintype "unspecified"))
    )
    (net (code "55") (name "/SWCLK") (class "Default")
      (node (ref "H1") (pin "5") (pinfunction "5_5") (pintype "unspecified"))
      (node (ref "U1") (pin "76") (pinfunction "PA14_76") (pintype "unspecified"))
    )
    (net (code "56") (name "/SWDIO") (class "Default")
      (node (ref "H1") (pin "1") (pinfunction "1_1") (pintype "unspecified"))
      (node (ref "U1") (pin "72") (pinfunction "PA13_72") (pintype "unspecified"))
    )
    (net (code "57") (name "/VCAP_1") (class "Default")
      (node (ref "C19") (pin "2") (pinfunction "2_2") (pintype "unspecified"))
      (node (ref "U1") (pin "49") (pinfunction "VCAP_1_49") (pintype "unspecified"))
    )
    (net (code "58") (name "/VCAP_2") (class "Default")
      (node (ref "C20") (pin "2") (pinfunction "2_2") (pintype "unspecified"))
      (node (ref "U1") (pin "73") (pinfunction "VCAP_2_73") (pintype "unspecified"))
    )
    (net (code "59") (name "/WAKE_UP") (class "Default")
      (node (ref "U1") (pin "45") (pinfunction "PE14_45") (pintype "unspecified"))
      (node (ref "U20") (pin "8") (pinfunction "8_8") (pintype "input"))
    )
    (net (code "60") (name "/WC#") (class "Default")
      (node (ref "U1") (pin "65") (pinfunction "PC8_65") (pintype "unspecified"))
      (node (ref "U21") (pin "7") (pinfunction "WP_7") (pintype "unspecified"))
    )
    (net (code "61") (name "/WS2812B") (class "Default")
      (node (ref "LED2") (pin "4") (pinfunction "DIN_4") (pintype "unspecified"))
      (node (ref "U1") (pin "26") (pinfunction "PA3_26") (pintype "unspecified"))
    )
    (net (code "62") (name "5V") (class "Default")
      (node (ref "C45") (pin "2") (pinfunction "2_2") (pintype "unspecified"))
      (node (ref "C47") (pin "2") (pinfunction "2_2") (pintype "unspecified"))
      (node (ref "C50") (pin "1") (pinfunction "1_1") (pintype "unspecified"))
      (node (ref "CN2") (pin "5") (pinfunction "5_5") (pintype "unspecified"))
      (node (ref "CN3") (pin "5") (pinfunction "5_5") (pintype "unspecified"))
      (node (ref "H3") (pin "1") (pinfunction "1_1") (pintype "unspecified"))
      (node (ref "LED2") (pin "1") (pinfunction "VDD_1") (pintype "unspecified"))
      (node (ref "Q3") (pin "2") (pinfunction "E_2") (pintype "input"))
      (node (ref "R19") (pin "1") (pinfunction "1_1") (pintype "input"))
      (node (ref "R27") (pin "1") (pinfunction "1_1") (pintype "unspecified"))
      (node (ref "U18") (pin "4") (pinfunction "VOUT_4") (pintype "unspecified"))
      (node (ref "U18") (pin "5") (pinfunction "VOUT_5") (pintype "unspecified"))
      (node (ref "U20") (pin "6") (pinfunction "6_6") (pintype "input"))
    )
    (net (code "63") (name "12.6V") (class "Default")
      (node (ref "C1") (pin "1") (pinfunction "1_1") (pintype "unspecified"))
      (node (ref "C22") (pin "1") (pinfunction "1_1") (pintype "unspecified"))
      (node (ref "C35") (pin "1") (pinfunction "1_1") (pintype "input"))
      (node (ref "C44") (pin "1") (pinfunction "1_1") (pintype "unspecified"))
      (node (ref "C49") (pin "1") (pinfunction "1_1") (pintype "unspecified"))
      (node (ref "C51") (pin "1") (pinfunction "1_1") (pintype "unspecified"))
      (node (ref "U16") (pin "2") (pinfunction "2_2") (pintype "unspecified"))
      (node (ref "U18") (pin "1") (pinfunction "EN_1") (pintype "unspecified"))
      (node (ref "U18") (pin "2") (pinfunction "VIN_2") (pintype "unspecified"))
      (node (ref "U2") (pin "1") (pinfunction "EN_1") (pintype "unspecified"))
      (node (ref "U2") (pin "2") (pinfunction "VIN_2") (pintype "unspecified"))
      (node (ref "U3") (pin "13") (pinfunction "VM2_13") (pintype "unspecified"))
      (node (ref "U3") (pin "14") (pinfunction "VM3_14") (pintype "unspecified"))
      (node (ref "U3") (pin "24") (pinfunction "VM1_24") (pintype "unspecified"))
    )
    (net (code "64") (name "12.6V_IN") (class "Default")
      (node (ref "CN1") (pin "2") (pinfunction "+_2") (pintype "unspecified"))
      (node (ref "U16") (pin "3") (pinfunction "3_3") (pintype "unspecified"))
    )
    (net (code "65") (name "GND") (class "Default")
      (node (ref "C1") (pin "2") (pinfunction "2_2") (pintype "unspecified"))
      (node (ref "C10") (pin "1") (pinfunction "1_1") (pintype "input"))
      (node (ref "C11") (pin "2") (pinfunction "2_2") (pintype "input"))
      (node (ref "C12") (pin "1") (pinfunction "1_1") (pintype "unspecified"))
      (node (ref "C13") (pin "1") (pinfunction "1_1") (pintype "unspecified"))
      (node (ref "C14") (pin "1") (pinfunction "1_1") (pintype "unspecified"))
      (node (ref "C15") (pin "1") (pinfunction "1_1") (pintype "unspecified"))
      (node (ref "C16") (pin "1") (pinfunction "1_1") (pintype "unspecified"))
      (node (ref "C17") (pin "1") (pinfunction "1_1") (pintype "unspecified"))
      (node (ref "C18") (pin "1") (pinfunction "1_1") (pintype "unspecified"))
      (node (ref "C19") (pin "1") (pinfunction "1_1") (pintype "unspecified"))
      (node (ref "C2") (pin "1") (pinfunction "1_1") (pintype "unspecified"))
      (node (ref "C20") (pin "1") (pinfunction "1_1") (pintype "unspecified"))
      (node (ref "C22") (pin "2") (pinfunction "2_2") (pintype "unspecified"))
      (node (ref "C24") (pin "2") (pinfunction "2_2") (pintype "unspecified"))
      (node (ref "C3") (pin "2") (pinfunction "2_2") (pintype "input"))
      (node (ref "C32") (pin "1") (pinfunction "1_1") (pintype "input"))
      (node (ref "C33") (pin "1") (pinfunction "1_1") (pintype "unspecified"))
      (node (ref "C34") (pin "1") (pinfunction "1_1") (pintype "unspecified"))
      (node (ref "C35") (pin "2") (pinfunction "2_2") (pintype "input"))
      (node (ref "C37") (pin "2") (pinfunction "2_2") (pintype "unspecified"))
      (node (ref "C43") (pin "2") (pinfunction "2_2") (pintype "unspecified"))
      (node (ref "C44") (pin "2") (pinfunction "2_2") (pintype "unspecified"))
      (node (ref "C45") (pin "1") (pinfunction "1_1") (pintype "unspecified"))
      (node (ref "C46") (pin "2") (pinfunction "2_2") (pintype "input"))
      (node (ref "C47") (pin "1") (pinfunction "1_1") (pintype "unspecified"))
      (node (ref "C48") (pin "2") (pinfunction "2_2") (pintype "unspecified"))
      (node (ref "C49") (pin "2") (pinfunction "2_2") (pintype "unspecified"))
      (node (ref "C50") (pin "2") (pinfunction "2_2") (pintype "unspecified"))
      (node (ref "C51") (pin "2") (pinfunction "2_2") (pintype "unspecified"))
      (node (ref "CN1") (pin "1") (pinfunction "-_1") (pintype "unspecified"))
      (node (ref "CN1") (pin "3") (pinfunction "3_3") (pintype "unspecified"))
      (node (ref "CN1") (pin "4") (pinfunction "4_4") (pintype "unspecified"))
      (node (ref "CN2") (pin "2") (pinfunction "2_2") (pintype "unspecified"))
      (node (ref "CN2") (pin "7") (pinfunction "7_7") (pintype "unspecified"))
      (node (ref "CN2") (pin "8") (pinfunction "8_8") (pintype "unspecified"))
      (node (ref "CN3") (pin "2") (pinfunction "2_2") (pintype "unspecified"))
      (node (ref "CN3") (pin "7") (pinfunction "7_7") (pintype "unspecified"))
      (node (ref "CN3") (pin "8") (pinfunction "8_8") (pintype "unspecified"))
      (node (ref "D2") (pin "2") (pinfunction "A_2") (pintype "unspecified"))
      (node (ref "H1") (pin "3") (pinfunction "3_3") (pintype "unspecified"))
      (node (ref "H1") (pin "8") (pinfunction "8_8") (pintype "unspecified"))
      (node (ref "H3") (pin "14") (pinfunction "14_14") (pintype "unspecified"))
      (node (ref "LED2") (pin "3") (pinfunction "GND_3") (pintype "unspecified"))
      (node (ref "Q4") (pin "2") (pinfunction "E_2") (pintype "input"))
      (node (ref "R15") (pin "1") (pinfunction "1_1") (pintype "input"))
      (node (ref "R16") (pin "1") (pinfunction "1_1") (pintype "input"))
      (node (ref "R17") (pin "1") (pinfunction "1_1") (pintype "input"))
      (node (ref "R18") (pin "1") (pinfunction "1_1") (pintype "input"))
      (node (ref "R21") (pin "1") (pinfunction "1_1") (pintype "input"))
      (node (ref "R28") (pin "2") (pinfunction "2_2") (pintype "input"))
      (node (ref "R4") (pin "2") (pinfunction "2_2") (pintype "input"))
      (node (ref "R5") (pin "2") (pinfunction "2_2") (pintype "input"))
      (node (ref "R7") (pin "2") (pinfunction "2_2") (pintype "input"))
      (node (ref "SW3") (pin "2") (pinfunction "2_2") (pintype "unspecified"))
      (node (ref "U1") (pin "10") (pinfunction "VSS_10") (pintype "unspecified"))
      (node (ref "U1") (pin "20") (pinfunction "VSSA_20") (pintype "unspecified"))
      (node (ref "U1") (pin "27") (pinfunction "VSS_27") (pintype "unspecified"))
      (node (ref "U1") (pin "74") (pinfunction "VSS_74") (pintype "unspecified"))
      (node (ref "U1") (pin "99") (pinfunction "VSS_99") (pintype "unspecified"))
      (node (ref "U11") (pin "1") (pinfunction "GND_1") (pintype "unspecified"))
      (node (ref "U11") (pin "12") (pinfunction "GND_12") (pintype "unspecified"))
      (node (ref "U11") (pin "5") (pinfunction "GND_5") (pintype "unspecified"))
      (node (ref "U11") (pin "6") (pinfunction "GND_6") (pintype "unspecified"))
      (node (ref "U18") (pin "3") (pinfunction "GND_3") (pintype "unspecified"))
      (node (ref "U18") (pin "9") (pinfunction "EP_9") (pintype "unspecified"))
      (node (ref "U19") (pin "2") (pinfunction "2_2") (pintype "unspecified"))
      (node (ref "U2") (pin "3") (pinfunction "GND_3") (pintype "unspecified"))
      (node (ref "U2") (pin "9") (pinfunction "EP_9") (pintype "unspecified"))
      (node (ref "U20") (pin "1") (pinfunction "1_1") (pintype "input"))
      (node (ref "U20") (pin "5") (pinfunction "5_5") (pintype "input"))
      (node (ref "U21") (pin "1") (pinfunction "A0_1") (pintype "unspecified"))
      (node (ref "U21") (pin "2") (pinfunction "A1_2") (pintype "unspecified"))
      (node (ref "U21") (pin "3") (pinfunction "A2_3") (pintype "unspecified"))
      (node (ref "U21") (pin "4") (pinfunction "VSS_4") (pintype "unspecified"))
      (node (ref "U3") (pin "10") (pinfunction "PGND2_10") (pintype "unspecified"))
      (node (ref "U3") (pin "18") (pinfunction "GND_18") (pintype "unspecified"))
      (node (ref "U3") (pin "3") (pinfunction "PGND1_3") (pintype "unspecified"))
      (node (ref "U3") (pin "4") (pinfunction "PGND1_4") (pintype "unspecified"))
      (node (ref "U3") (pin "9") (pinfunction "PGND2_9") (pintype "unspecified"))
      (node (ref "U4") (pin "11") (pinfunction "RESV_11") (pintype "unspecified"))
      (node (ref "U4") (pin "6") (pinfunction "GND_6") (pintype "unspecified"))
      (node (ref "U4") (pin "7") (pinfunction "RESV_7") (pintype "unspecified"))
      (node (ref "U6") (pin "1") (pinfunction "1_1") (pintype "unspecified"))
      (node (ref "U7") (pin "1") (pinfunction "1_1") (pintype "unspecified"))
      (node (ref "U8") (pin "1") (pinfunction "1_1") (pintype "unspecified"))
      (node (ref "U9") (pin "1") (pinfunction "1_1") (pintype "unspecified"))
      (node (ref "X1") (pin "2") (pinfunction "GND_2") (pintype "input"))
      (node (ref "X1") (pin "4") (pinfunction "GND_4") (pintype "input"))
    )
    (net (code "66") (name "Net-(C38-Pad1)") (class "Default")
      (node (ref "C38") (pin "1") (pinfunction "1_1") (pintype "unspecified"))
      (node (ref "R15") (pin "2") (pinfunction "2_2") (pintype "input"))
      (node (ref "U12") (pin "2") (pinfunction "2_2") (pintype "unspecified"))
    )
    (net (code "67") (name "Net-(C39-Pad1)") (class "Default")
      (node (ref "C39") (pin "1") (pinfunction "1_1") (pintype "unspecified"))
      (node (ref "R16") (pin "2") (pinfunction "2_2") (pintype "input"))
      (node (ref "U13") (pin "2") (pinfunction "2_2") (pintype "unspecified"))
    )
    (net (code "68") (name "Net-(C40-Pad1)") (class "Default")
      (node (ref "C40") (pin "1") (pinfunction "1_1") (pintype "unspecified"))
      (node (ref "R17") (pin "2") (pinfunction "2_2") (pintype "input"))
      (node (ref "U14") (pin "2") (pinfunction "2_2") (pintype "unspecified"))
    )
    (net (code "69") (name "Net-(C41-Pad1)") (class "Default")
      (node (ref "C41") (pin "1") (pinfunction "1_1") (pintype "unspecified"))
      (node (ref "R18") (pin "2") (pinfunction "2_2") (pintype "input"))
      (node (ref "U15") (pin "2") (pinfunction "2_2") (pintype "unspecified"))
    )
    (net (code "70") (name "Net-(D2-K)") (class "Default")
      (node (ref "D2") (pin "1") (pinfunction "K_1") (pintype "unspecified"))
      (node (ref "Q3") (pin "3") (pinfunction "C_3") (pintype "input"))
      (node (ref "U19") (pin "1") (pinfunction "+_1") (pintype "unspecified"))
    )
    (net (code "71") (name "Net-(LED1-K)") (class "Default")
      (node (ref "LED1") (pin "1") (pinfunction "K_1") (pintype "input"))
      (node (ref "R21") (pin "2") (pinfunction "2_2") (pintype "input"))
    )
    (net (code "72") (name "Net-(Q3-B)") (class "Default")
      (node (ref "Q3") (pin "1") (pinfunction "B_1") (pintype "input"))
      (node (ref "R19") (pin "2") (pinfunction "2_2") (pintype "input"))
      (node (ref "R22") (pin "2") (pinfunction "2_2") (pintype "input"))
    )
    (net (code "73") (name "Net-(Q4-B)") (class "Default")
      (node (ref "Q4") (pin "1") (pinfunction "B_1") (pintype "input"))
      (node (ref "R13") (pin "2") (pinfunction "2_2") (pintype "input"))
      (node (ref "R14") (pin "2") (pinfunction "2_2") (pintype "input"))
    )
    (net (code "74") (name "Net-(Q4-C)") (class "Default")
      (node (ref "Q4") (pin "3") (pinfunction "C_3") (pintype "input"))
      (node (ref "R12") (pin "1") (pinfunction "1_1") (pintype "input"))
    )
    (net (code "75") (name "Net-(U2-FB)") (class "Default")
      (node (ref "R7") (pin "1") (pinfunction "1_1") (pintype "input"))
      (node (ref "R8") (pin "2") (pinfunction "2_2") (pintype "input"))
      (node (ref "U2") (pin "6") (pinfunction "FB_6") (pintype "unspecified"))
    )
    (net (code "76") (name "Net-(U2-SS{slash}TR)") (class "Default")
      (node (ref "C3") (pin "1") (pinfunction "1_1") (pintype "input"))
      (node (ref "U2") (pin "8") (pinfunction "SS/TR_8") (pintype "unspecified"))
    )
    (net (code "77") (name "Net-(U11-LEDK)") (class "Default")
      (node (ref "R12") (pin "2") (pinfunction "2_2") (pintype "input"))
      (node (ref "U11") (pin "2") (pinfunction "LEDK_2") (pintype "unspecified"))
    )
    (net (code "78") (name "Net-(U18-FB)") (class "Default")
      (node (ref "R27") (pin "2") (pinfunction "2_2") (pintype "unspecified"))
      (node (ref "R28") (pin "1") (pinfunction "1_1") (pintype "input"))
      (node (ref "U18") (pin "6") (pinfunction "FB_6") (pintype "unspecified"))
    )
    (net (code "79") (name "Net-(U18-SS{slash}TR)") (class "Default")
      (node (ref "C46") (pin "1") (pinfunction "1_1") (pintype "input"))
      (node (ref "U18") (pin "8") (pinfunction "SS/TR_8") (pintype "unspecified"))
    )
    (net (code "80") (name "VDD") (class "Default")
      (node (ref "C12") (pin "2") (pinfunction "2_2") (pintype "unspecified"))
      (node (ref "C13") (pin "2") (pinfunction "2_2") (pintype "unspecified"))
      (node (ref "C14") (pin "2") (pinfunction "2_2") (pintype "unspecified"))
      (node (ref "C15") (pin "2") (pinfunction "2_2") (pintype "unspecified"))
      (node (ref "C16") (pin "2") (pinfunction "2_2") (pintype "unspecified"))
      (node (ref "C17") (pin "2") (pinfunction "2_2") (pintype "unspecified"))
      (node (ref "C18") (pin "2") (pinfunction "2_2") (pintype "unspecified"))
      (node (ref "C2") (pin "2") (pinfunction "2_2") (pintype "unspecified"))
      (node (ref "C24") (pin "1") (pinfunction "1_1") (pintype "unspecified"))
      (node (ref "C32") (pin "2") (pinfunction "2_2") (pintype "input"))
      (node (ref "C33") (pin "2") (pinfunction "2_2") (pintype "unspecified"))
      (node (ref "C34") (pin "2") (pinfunction "2_2") (pintype "unspecified"))
      (node (ref "C37") (pin "1") (pinfunction "1_1") (pintype "unspecified"))
      (node (ref "C43") (pin "1") (pinfunction "1_1") (pintype "unspecified"))
      (node (ref "C48") (pin "1") (pinfunction "1_1") (pintype "unspecified"))
      (node (ref "H1") (pin "7") (pinfunction "7_7") (pintype "unspecified"))
      (node (ref "LED1") (pin "2") (pinfunction "A_2") (pintype "input"))
      (node (ref "R13") (pin "1") (pinfunction "1_1") (pintype "input"))
      (node (ref "R29") (pin "2") (pinfunction "2_2") (pintype "input"))
      (node (ref "R30") (pin "2") (pinfunction "2_2") (pintype "input"))
      (node (ref "R6") (pin "2") (pinfunction "2_2") (pintype "input"))
      (node (ref "R8") (pin "1") (pinfunction "1_1") (pintype "input"))
      (node (ref "U1") (pin "100") (pinfunction "VDD_100") (pintype "unspecified"))
      (node (ref "U1") (pin "11") (pinfunction "VDD_11") (pintype "unspecified"))
      (node (ref "U1") (pin "19") (pinfunction "VDD_19") (pintype "unspecified"))
      (node (ref "U1") (pin "21") (pinfunction "VREF+_21") (pintype "unspecified"))
      (node (ref "U1") (pin "22") (pinfunction "VDDA_22") (pintype "unspecified"))
      (node (ref "U1") (pin "28") (pinfunction "VDD_28") (pintype "unspecified"))
      (node (ref "U1") (pin "50") (pinfunction "VDD_50") (pintype "unspecified"))
      (node (ref "U1") (pin "75") (pinfunction "VDD_75") (pintype "unspecified"))
      (node (ref "U11") (pin "3") (pinfunction "LEDA_3") (pintype "unspecified"))
      (node (ref "U11") (pin "4") (pinfunction "VDD_4") (pintype "unspecified"))
      (node (ref "U2") (pin "4") (pinfunction "VOUT_4") (pintype "unspecified"))
      (node (ref "U2") (pin "5") (pinfunction "VOUT_5") (pintype "unspecified"))
      (node (ref "U21") (pin "8") (pinfunction "VCC_8") (pintype "unspecified"))
      (node (ref "U3") (pin "19") (pinfunction "STBY_19") (pintype "unspecified"))
      (node (ref "U3") (pin "20") (pinfunction "VCC_20") (pintype "unspecified"))
      (node (ref "U4") (pin "5") (pinfunction "VDDIO_5") (pintype "unspecified"))
      (node (ref "U4") (pin "8") (pinfunction "VDD_8") (pintype "unspecified"))
    )
    (net (code "81") (name "unconnected-(H1-Pad2)") (class "Default")
      (node (ref "H1") (pin "2") (pinfunction "2_2") (pintype "unspecified+no_connect"))
    )
    (net (code "82") (name "unconnected-(LED2-DOU-Pad2)") (class "Default")
      (node (ref "LED2") (pin "2") (pinfunction "DOU_2") (pintype "unspecified+no_connect"))
    )
    (net (code "83") (name "unconnected-(U1-PA4-Pad29)") (class "Default")
      (node (ref "U1") (pin "29") (pinfunction "PA4_29") (pintype "unspecified+no_connect"))
    )
    (net (code "84") (name "unconnected-(U1-PB0-Pad35)") (class "Default")
      (node (ref "U1") (pin "35") (pinfunction "PB0_35") (pintype "unspecified+no_connect"))
    )
    (net (code "85") (name "unconnected-(U1-PB1-Pad36)") (class "Default")
      (node (ref "U1") (pin "36") (pinfunction "PB1_36") (pintype "unspecified+no_connect"))
    )
    (net (code "86") (name "unconnected-(U1-PB3-Pad89)") (class "Default")
      (node (ref "U1") (pin "89") (pinfunction "PB3_89") (pintype "unspecified+no_connect"))
    )
    (net (code "87") (name "unconnected-(U1-PB4-Pad90)") (class "Default")
      (node (ref "U1") (pin "90") (pinfunction "PB4_90") (pintype "unspecified+no_connect"))
    )
    (net (code "88") (name "unconnected-(U1-PB9-Pad96)") (class "Default")
      (node (ref "U1") (pin "96") (pinfunction "PB9_96") (pintype "unspecified+no_connect"))
    )
    (net (code "89") (name "unconnected-(U1-PC0-Pad15)") (class "Default")
      (node (ref "U1") (pin "15") (pinfunction "PC0_15") (pintype "unspecified+no_connect"))
    )
    (net (code "90") (name "unconnected-(U1-PC1-Pad16)") (class "Default")
      (node (ref "U1") (pin "16") (pinfunction "PC1_16") (pintype "unspecified+no_connect"))
    )
    (net (code "91") (name "unconnected-(U1-PC13-Pad7)") (class "Default")
      (node (ref "U1") (pin "7") (pinfunction "PC13_7") (pintype "unspecified+no_connect"))
    )
    (net (code "92") (name "unconnected-(U1-PC14-Pad8)") (class "Default")
      (node (ref "U1") (pin "8") (pinfunction "PC14_8") (pintype "unspecified+no_connect"))
    )
    (net (code "93") (name "unconnected-(U1-PC15-Pad9)") (class "Default")
      (node (ref "U1") (pin "9") (pinfunction "PC15_9") (pintype "unspecified+no_connect"))
    )
    (net (code "94") (name "unconnected-(U1-PD1-Pad82)") (class "Default")
      (node (ref "U1") (pin "82") (pinfunction "PD1_82") (pintype "unspecified+no_connect"))
    )
    (net (code "95") (name "unconnected-(U1-PD2-Pad83)") (class "Default")
      (node (ref "U1") (pin "83") (pinfunction "PD2_83") (pintype "unspecified+no_connect"))
    )
    (net (code "96") (name "unconnected-(U1-PD3-Pad84)") (class "Default")
      (node (ref "U1") (pin "84") (pinfunction "PD3_84") (pintype "unspecified+no_connect"))
    )
    (net (code "97") (name "unconnected-(U1-PD4-Pad85)") (class "Default")
      (node (ref "U1") (pin "85") (pinfunction "PD4_85") (pintype "unspecified+no_connect"))
    )
    (net (code "98") (name "unconnected-(U1-PD7-Pad88)") (class "Default")
      (node (ref "U1") (pin "88") (pinfunction "PD7_88") (pintype "unspecified+no_connect"))
    )
    (net (code "99") (name "unconnected-(U1-PD9-Pad56)") (class "Default")
      (node (ref "U1") (pin "56") (pinfunction "PD9_56") (pintype "unspecified+no_connect"))
    )
    (net (code "100") (name "unconnected-(U1-PD10-Pad57)") (class "Default")
      (node (ref "U1") (pin "57") (pinfunction "PD10_57") (pintype "unspecified+no_connect"))
    )
    (net (code "101") (name "unconnected-(U1-PD11-Pad58)") (class "Default")
      (node (ref "U1") (pin "58") (pinfunction "PD11_58") (pintype "unspecified+no_connect"))
    )
    (net (code "102") (name "unconnected-(U1-PD14-Pad61)") (class "Default")
      (node (ref "U1") (pin "61") (pinfunction "PD14_61") (pintype "unspecified+no_connect"))
    )
    (net (code "103") (name "unconnected-(U1-PD15-Pad62)") (class "Default")
      (node (ref "U1") (pin "62") (pinfunction "PD15_62") (pintype "unspecified+no_connect"))
    )
    (net (code "104") (name "unconnected-(U1-PE0-Pad97)") (class "Default")
      (node (ref "U1") (pin "97") (pinfunction "PE0_97") (pintype "unspecified+no_connect"))
    )
    (net (code "105") (name "unconnected-(U1-PE1-Pad98)") (class "Default")
      (node (ref "U1") (pin "98") (pinfunction "PE1_98") (pintype "unspecified+no_connect"))
    )
    (net (code "106") (name "unconnected-(U1-PE2-Pad1)") (class "Default")
      (node (ref "U1") (pin "1") (pinfunction "PE2_1") (pintype "unspecified+no_connect"))
    )
    (net (code "107") (name "unconnected-(U1-PE3-Pad2)") (class "Default")
      (node (ref "U1") (pin "2") (pinfunction "PE3_2") (pintype "unspecified+no_connect"))
    )
    (net (code "108") (name "unconnected-(U1-PE4-Pad3)") (class "Default")
      (node (ref "U1") (pin "3") (pinfunction "PE4_3") (pintype "unspecified+no_connect"))
    )
    (net (code "109") (name "unconnected-(U1-PE10-Pad41)") (class "Default")
      (node (ref "U1") (pin "41") (pinfunction "PE10_41") (pintype "unspecified+no_connect"))
    )
    (net (code "110") (name "unconnected-(U1-PE11-Pad42)") (class "Default")
      (node (ref "U1") (pin "42") (pinfunction "PE11_42") (pintype "unspecified+no_connect"))
    )
    (net (code "111") (name "unconnected-(U1-PE12-Pad43)") (class "Default")
      (node (ref "U1") (pin "43") (pinfunction "PE12_43") (pintype "unspecified+no_connect"))
    )
    (net (code "112") (name "unconnected-(U1-VBAT-Pad6)") (class "Default")
      (node (ref "U1") (pin "6") (pinfunction "VBAT_6") (pintype "unspecified+no_connect"))
    )
    (net (code "113") (name "unconnected-(U2-PG-Pad7)") (class "Default")
      (node (ref "U2") (pin "7") (pinfunction "PG_7") (pintype "unspecified+no_connect"))
    )
    (net (code "114") (name "unconnected-(U4-INT2{slash}FSYNC{slash}CLKIN-Pad9)") (class "Default")
      (node (ref "U4") (pin "9") (pinfunction "INT2/FSYNC/CLKIN_9") (pintype "unspecified+no_connect"))
    )
    (net (code "115") (name "unconnected-(U4-RESV-Pad2)") (class "Default")
      (node (ref "U4") (pin "2") (pinfunction "RESV_2") (pintype "unspecified+no_connect"))
    )
    (net (code "116") (name "unconnected-(U4-RESV-Pad3)") (class "Default")
      (node (ref "U4") (pin "3") (pinfunction "RESV_3") (pintype "unspecified+no_connect"))
    )
    (net (code "117") (name "unconnected-(U4-RESV-Pad10)") (class "Default")
      (node (ref "U4") (pin "10") (pinfunction "RESV_10") (pintype "unspecified+no_connect"))
    )
    (net (code "118") (name "unconnected-(U16-Pad1)") (class "Default")
      (node (ref "U16") (pin "1") (pinfunction "1_1") (pintype "unspecified+no_connect"))
    )
    (net (code "119") (name "unconnected-(U18-PG-Pad7)") (class "Default")
      (node (ref "U18") (pin "7") (pinfunction "PG_7") (pintype "unspecified+no_connect"))
    )
    (net (code "120") (name "unconnected-(U19-Pad3)") (class "Default")
      (node (ref "U19") (pin "3") (pinfunction "3_3") (pintype "unspecified+no_connect"))
    )
    (net (code "121") (name "unconnected-(U19-Pad4)") (class "Default")
      (node (ref "U19") (pin "4") (pinfunction "4_4") (pintype "unspecified+no_connect"))
    )
    (net (code "122") (name "unconnected-(U20-Pad2)") (class "Default")
      (node (ref "U20") (pin "2") (pinfunction "2_2") (pintype "input+no_connect"))
    )
    (net (code "123") (name "unconnected-(U20-Pad3)") (class "Default")
      (node (ref "U20") (pin "3") (pinfunction "3_3") (pintype "input+no_connect"))
    )
    (net (code "124") (name "unconnected-(U20-Pad4)") (class "Default")
      (node (ref "U20") (pin "4") (pinfunction "4_4") (pintype "input+no_connect"))
    )
    (net (code "125") (name "unconnected-(U20-Pad7)") (class "Default")
      (node (ref "U20") (pin "7") (pinfunction "7_7") (pintype "input+no_connect"))
    )
    (net (code "126") (name "unconnected-(U20-Pad9)") (class "Default")
      (node (ref "U20") (pin "9") (pinfunction "9_9") (pintype "input+no_connect"))
    )
  )
)
